# MCU.net
KiCad netlist of a schematic drawn in Altium Designer
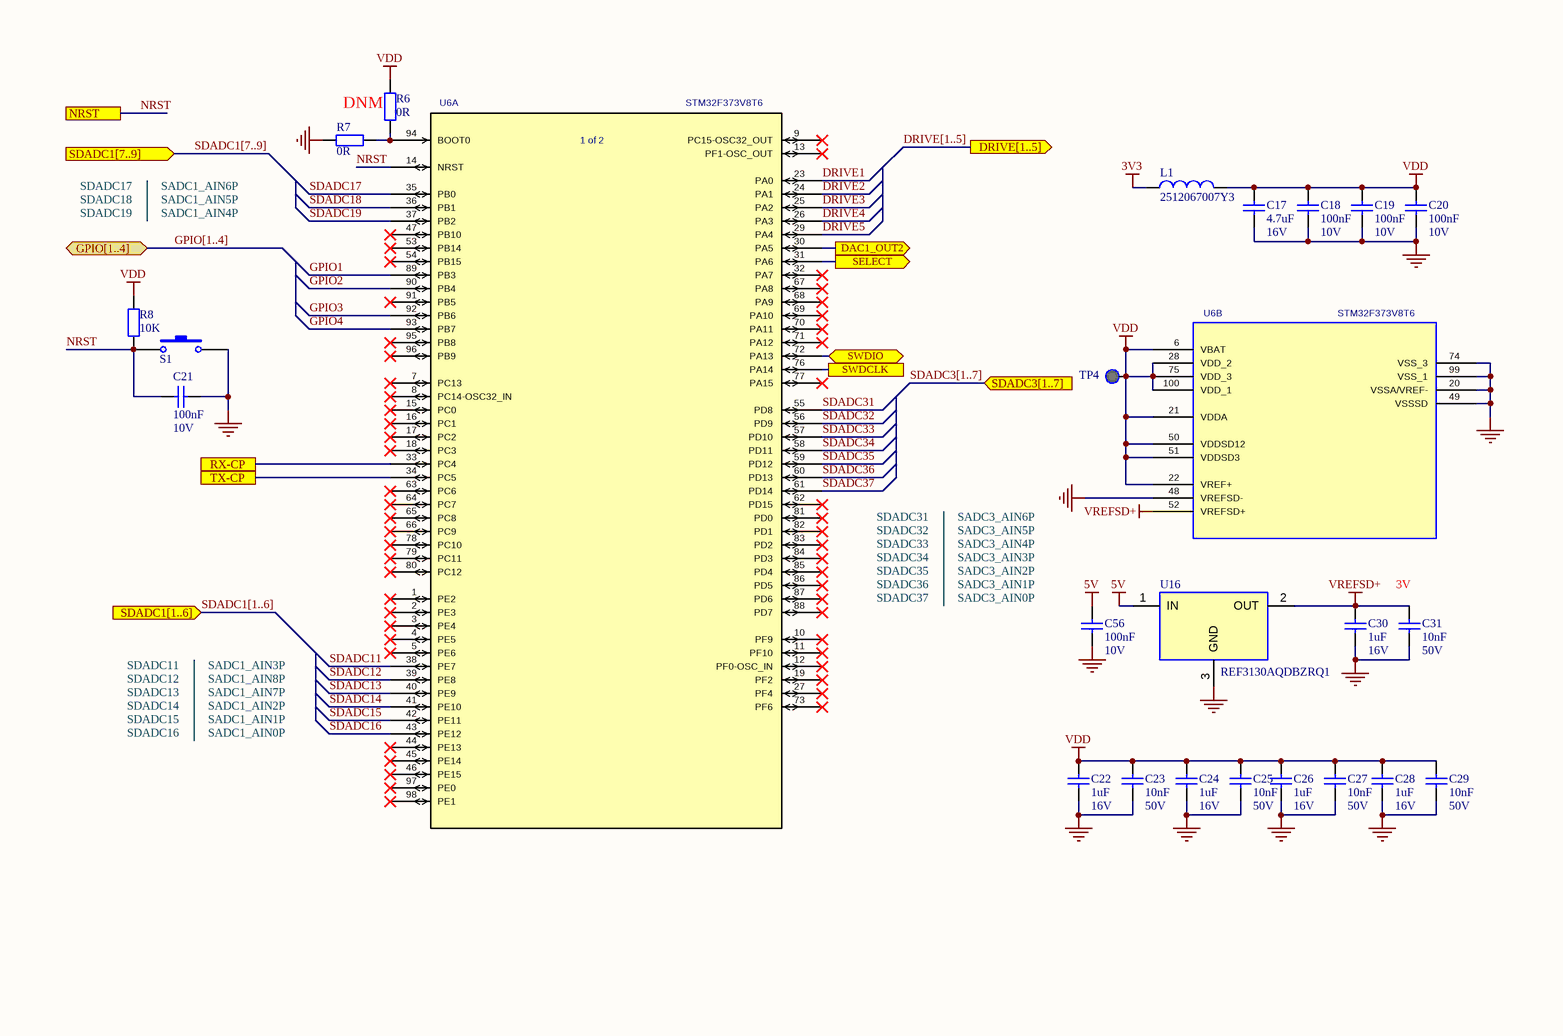
[diagram p0: MCU.SchDoc]

(export (version "E")
  (design (tool "Eeschema 10.0.6"))
  (components
    (comp (ref "C17")
      (value "Capacitor")
      (footprint "CAPC1608N")
      (fields
        (field (name "PART NUMBER") "CAP-000000047")
        (field (name "VALUE 1") "4.7uF")
        (field (name "VALUE 2") "16V")
      )
      (libsource (lib "CMA") (part "Capacitor"))
    )
    (comp (ref "C18")
      (value "Capacitor")
      (footprint "CAPC1608N")
      (fields
        (field (name "PART NUMBER") "CAP-000000005")
        (field (name "VALUE 1") "100nF")
        (field (name "VALUE 2") "10V")
      )
      (libsource (lib "CMA") (part "Capacitor"))
    )
    (comp (ref "C19")
      (value "Capacitor")
      (footprint "CAPC1608N")
      (fields
        (field (name "PART NUMBER") "CAP-000000005")
        (field (name "VALUE 1") "100nF")
        (field (name "VALUE 2") "10V")
      )
      (libsource (lib "CMA") (part "Capacitor"))
    )
    (comp (ref "C20")
      (value "Capacitor")
      (footprint "CAPC1608N")
      (fields
        (field (name "PART NUMBER") "CAP-000000005")
        (field (name "VALUE 1") "100nF")
        (field (name "VALUE 2") "10V")
      )
      (libsource (lib "CMA") (part "Capacitor"))
    )
    (comp (ref "C21")
      (value "Capacitor")
      (footprint "CAPC1608N")
      (fields
        (field (name "PART NUMBER") "CAP-000000005")
        (field (name "VALUE 1") "100nF")
        (field (name "VALUE 2") "10V")
      )
      (libsource (lib "CMA") (part "Capacitor"))
    )
    (comp (ref "C22")
      (value "Capacitor")
      (footprint "CAPC1608N")
      (fields
        (field (name "PART NUMBER") "CAP-000000011")
        (field (name "VALUE 1") "1uF")
        (field (name "VALUE 2") "16V")
      )
      (libsource (lib "CMA") (part "Capacitor"))
    )
    (comp (ref "C23")
      (value "Capacitor")
      (footprint "CAPC1608N")
      (fields
        (field (name "PART NUMBER") "CAP-000000003")
        (field (name "VALUE 1") "10nF")
        (field (name "VALUE 2") "50V")
      )
      (libsource (lib "CMA") (part "Capacitor"))
    )
    (comp (ref "C24")
      (value "Capacitor")
      (footprint "CAPC1608N")
      (fields
        (field (name "PART NUMBER") "CAP-000000011")
        (field (name "VALUE 1") "1uF")
        (field (name "VALUE 2") "16V")
      )
      (libsource (lib "CMA") (part "Capacitor"))
    )
    (comp (ref "C25")
      (value "Capacitor")
      (footprint "CAPC1608N")
      (fields
        (field (name "PART NUMBER") "CAP-000000003")
        (field (name "VALUE 1") "10nF")
        (field (name "VALUE 2") "50V")
      )
      (libsource (lib "CMA") (part "Capacitor"))
    )
    (comp (ref "C26")
      (value "Capacitor")
      (footprint "CAPC1608N")
      (fields
        (field (name "PART NUMBER") "CAP-000000011")
        (field (name "VALUE 1") "1uF")
        (field (name "VALUE 2") "16V")
      )
      (libsource (lib "CMA") (part "Capacitor"))
    )
    (comp (ref "C27")
      (value "Capacitor")
      (footprint "CAPC1608N")
      (fields
        (field (name "PART NUMBER") "CAP-000000003")
        (field (name "VALUE 1") "10nF")
        (field (name "VALUE 2") "50V")
      )
      (libsource (lib "CMA") (part "Capacitor"))
    )
    (comp (ref "C28")
      (value "Capacitor")
      (footprint "CAPC1608N")
      (fields
        (field (name "PART NUMBER") "CAP-000000011")
        (field (name "VALUE 1") "1uF")
        (field (name "VALUE 2") "16V")
      )
      (libsource (lib "CMA") (part "Capacitor"))
    )
    (comp (ref "C29")
      (value "Capacitor")
      (footprint "CAPC1608N")
      (fields
        (field (name "PART NUMBER") "CAP-000000003")
        (field (name "VALUE 1") "10nF")
        (field (name "VALUE 2") "50V")
      )
      (libsource (lib "CMA") (part "Capacitor"))
    )
    (comp (ref "C30")
      (value "Capacitor")
      (footprint "CAPC1608N")
      (fields
        (field (name "PART NUMBER") "CAP-000000011")
        (field (name "VALUE 1") "1uF")
        (field (name "VALUE 2") "16V")
      )
      (libsource (lib "CMA") (part "Capacitor"))
    )
    (comp (ref "C31")
      (value "Capacitor")
      (footprint "CAPC1608N")
      (fields
        (field (name "PART NUMBER") "CAP-000000003")
        (field (name "VALUE 1") "10nF")
        (field (name "VALUE 2") "50V")
      )
      (libsource (lib "CMA") (part "Capacitor"))
    )
    (comp (ref "C56")
      (value "Capacitor")
      (footprint "CAPC1608N")
      (fields
        (field (name "PART NUMBER") "CAP-000000005")
        (field (name "VALUE 1") "100nF")
        (field (name "VALUE 2") "10V")
      )
      (libsource (lib "CMA") (part "Capacitor"))
    )
    (comp (ref "L1")
      (value "2512067007Y3")
      (footprint "INDC3216N")
      (fields (field (name "PART NUMBER") "FER-000000001"))
      (libsource (lib "CMA") (part "Inductor"))
    )
    (comp (ref "R6")
      (value "Resistor")
      (footprint "RESC1608N")
      (fields (field (name "PART NUMBER") "RES-000000103") (field (name "VALUE 1") "0R"))
      (libsource (lib "") (part "Resistor_1"))
    )
    (comp (ref "R7")
      (value "Resistor")
      (footprint "RESC1608N")
      (fields (field (name "PART NUMBER") "RES-000000103") (field (name "VALUE 1") "0R"))
      (libsource (lib "CMA") (part "Resistor"))
    )
    (comp (ref "R8")
      (value "Resistor")
      (footprint "RESC1608N")
      (fields (field (name "PART NUMBER") "RES-000000001") (field (name "VALUE 1") "10K"))
      (libsource (lib "") (part "Resistor_2"))
    )
    (comp (ref "S1")
      (value "FSM4JSMA")
      (footprint "FSM4")
      (fields (field (name "PART NUMBER") "SWC-000000004"))
      (libsource (lib "CMA") (part "SW-PB"))
    )
    (comp (ref "TP4")
      (value "Test Point")
      (footprint "TP")
      (fields (field (name "PART NUMBER") "MIS-000000003"))
      (libsource (lib "CMA") (part "TP"))
    )
    (comp (ref "U6")
      (value "STM32F373V8T6")
      (footprint "LQFP100")
      (fields (field (name "PART NUMBER") "MCU-000000001"))
      (libsource (lib "CMA") (part "STM32F373V8T6"))
    )
    (comp (ref "U16")
      (value "REF3130AQDBZRQ1")
      (footprint "SOT23-3N")
      (fields (field (name "PART NUMBER") "VRF-000000001"))
      (libsource (lib "CMA") (part "REF3133AQDBZRQ1"))
    )
  )
  (nets
    (net (code "2") (name "/DAC1_OUT2") (class "Default")
      (node (ref "U6") (pin "30") (pinfunction "PA5_30") (pintype "passive"))
    )
    (net (code "3") (name "/DRIVE1") (class "Default")
      (node (ref "U6") (pin "23") (pinfunction "PA0_23") (pintype "passive"))
    )
    (net (code "4") (name "/DRIVE2") (class "Default")
      (node (ref "U6") (pin "24") (pinfunction "PA1_24") (pintype "passive"))
    )
    (net (code "5") (name "/DRIVE3") (class "Default")
      (node (ref "U6") (pin "25") (pinfunction "PA2_25") (pintype "passive"))
    )
    (net (code "6") (name "/DRIVE4") (class "Default")
      (node (ref "U6") (pin "26") (pinfunction "PA3_26") (pintype "passive"))
    )
    (net (code "7") (name "/DRIVE5") (class "Default")
      (node (ref "U6") (pin "29") (pinfunction "PA4_29") (pintype "passive"))
    )
    (net (code "9") (name "/GPIO1") (class "Default")
      (node (ref "U6") (pin "89") (pinfunction "PB3_89") (pintype "passive"))
    )
    (net (code "10") (name "/GPIO2") (class "Default")
      (node (ref "U6") (pin "90") (pinfunction "PB4_90") (pintype "passive"))
    )
    (net (code "11") (name "/GPIO3") (class "Default")
      (node (ref "U6") (pin "92") (pinfunction "PB6_92") (pintype "passive"))
    )
    (net (code "12") (name "/GPIO4") (class "Default")
      (node (ref "U6") (pin "93") (pinfunction "PB7_93") (pintype "passive"))
    )
    (net (code "14") (name "/NRST") (class "Default")
      (node (ref "C21") (pin "2") (pinfunction "2_2") (pintype "passive"))
      (node (ref "R8") (pin "2") (pinfunction "2_2") (pintype "passive"))
      (node (ref "S1") (pin "1") (pinfunction "1_1") (pintype "passive"))
      (node (ref "U6") (pin "14") (pinfunction "NRST_14") (pintype "passive"))
    )
    (net (code "15") (name "/RX-CP") (class "Default")
      (node (ref "U6") (pin "33") (pinfunction "PC4_33") (pintype "passive"))
    )
    (net (code "19") (name "/SDADC11") (class "Default")
      (node (ref "U6") (pin "38") (pinfunction "PE7_38") (pintype "passive"))
    )
    (net (code "20") (name "/SDADC12") (class "Default")
      (node (ref "U6") (pin "39") (pinfunction "PE8_39") (pintype "passive"))
    )
    (net (code "21") (name "/SDADC13") (class "Default")
      (node (ref "U6") (pin "40") (pinfunction "PE9_40") (pintype "passive"))
    )
    (net (code "22") (name "/SDADC14") (class "Default")
      (node (ref "U6") (pin "41") (pinfunction "PE10_41") (pintype "passive"))
    )
    (net (code "23") (name "/SDADC15") (class "Default")
      (node (ref "U6") (pin "42") (pinfunction "PE11_42") (pintype "passive"))
    )
    (net (code "24") (name "/SDADC16") (class "Default")
      (node (ref "U6") (pin "43") (pinfunction "PE12_43") (pintype "passive"))
    )
    (net (code "25") (name "/SDADC17") (class "Default")
      (node (ref "U6") (pin "35") (pinfunction "PB0_35") (pintype "passive"))
    )
    (net (code "26") (name "/SDADC18") (class "Default")
      (node (ref "U6") (pin "36") (pinfunction "PB1_36") (pintype "passive"))
    )
    (net (code "27") (name "/SDADC19") (class "Default")
      (node (ref "U6") (pin "37") (pinfunction "PB2_37") (pintype "passive"))
    )
    (net (code "28") (name "/SDADC31") (class "Default")
      (node (ref "U6") (pin "55") (pinfunction "PD8_55") (pintype "passive"))
    )
    (net (code "29") (name "/SDADC32") (class "Default")
      (node (ref "U6") (pin "56") (pinfunction "PD9_56") (pintype "passive"))
    )
    (net (code "30") (name "/SDADC33") (class "Default")
      (node (ref "U6") (pin "57") (pinfunction "PD10_57") (pintype "passive"))
    )
    (net (code "31") (name "/SDADC34") (class "Default")
      (node (ref "U6") (pin "58") (pinfunction "PD11_58") (pintype "passive"))
    )
    (net (code "32") (name "/SDADC35") (class "Default")
      (node (ref "U6") (pin "59") (pinfunction "PD12_59") (pintype "passive"))
    )
    (net (code "33") (name "/SDADC36") (class "Default")
      (node (ref "U6") (pin "60") (pinfunction "PD13_60") (pintype "passive"))
    )
    (net (code "34") (name "/SDADC37") (class "Default")
      (node (ref "U6") (pin "61") (pinfunction "PD14_61") (pintype "passive"))
    )
    (net (code "35") (name "/SELECT") (class "Default")
      (node (ref "U6") (pin "31") (pinfunction "PA6_31") (pintype "passive"))
    )
    (net (code "36") (name "/SWDCLK") (class "Default")
      (node (ref "U6") (pin "76") (pinfunction "PA14_76") (pintype "passive"))
    )
    (net (code "37") (name "/SWDIO") (class "Default")
      (node (ref "U6") (pin "72") (pinfunction "PA13_72") (pintype "passive"))
    )
    (net (code "38") (name "/TX-CP") (class "Default")
      (node (ref "U6") (pin "34") (pinfunction "PC5_34") (pintype "passive"))
    )
    (net (code "39") (name "3V3") (class "Default")
      (node (ref "L1") (pin "1") (pinfunction "1_1") (pintype "passive"))
    )
    (net (code "40") (name "5V") (class "Default")
      (node (ref "C56") (pin "2") (pinfunction "2_2") (pintype "passive"))
      (node (ref "U16") (pin "1") (pinfunction "IN_1") (pintype "passive"))
    )
    (net (code "41") (name "GND") (class "Default")
      (node (ref "C17") (pin "2") (pinfunction "2_2") (pintype "passive"))
      (node (ref "C18") (pin "1") (pinfunction "1_1") (pintype "passive"))
      (node (ref "C19") (pin "1") (pinfunction "1_1") (pintype "passive"))
      (node (ref "C20") (pin "1") (pinfunction "1_1") (pintype "passive"))
      (node (ref "C21") (pin "1") (pinfunction "1_1") (pintype "passive"))
      (node (ref "C22") (pin "1") (pinfunction "1_1") (pintype "passive"))
      (node (ref "C23") (pin "1") (pinfunction "1_1") (pintype "passive"))
      (node (ref "C24") (pin "1") (pinfunction "1_1") (pintype "passive"))
      (node (ref "C25") (pin "1") (pinfunction "1_1") (pintype "passive"))
      (node (ref "C26") (pin "1") (pinfunction "1_1") (pintype "passive"))
      (node (ref "C27") (pin "1") (pinfunction "1_1") (pintype "passive"))
      (node (ref "C28") (pin "1") (pinfunction "1_1") (pintype "passive"))
      (node (ref "C29") (pin "1") (pinfunction "1_1") (pintype "passive"))
      (node (ref "C30") (pin "1") (pinfunction "1_1") (pintype "passive"))
      (node (ref "C31") (pin "1") (pinfunction "1_1") (pintype "passive"))
      (node (ref "C56") (pin "1") (pinfunction "1_1") (pintype "passive"))
      (node (ref "R7") (pin "1") (pinfunction "1_1") (pintype "passive"))
      (node (ref "S1") (pin "2") (pinfunction "2_2") (pintype "passive"))
      (node (ref "U16") (pin "3") (pinfunction "GND_3") (pintype "passive"))
      (node (ref "U6") (pin "20") (pinfunction "VSSA/VREF-_20") (pintype "power_in"))
      (node (ref "U6") (pin "48") (pinfunction "VREFSD-_48") (pintype "power_in"))
      (node (ref "U6") (pin "49") (pinfunction "VSSSD_49") (pintype "power_in"))
      (node (ref "U6") (pin "74") (pinfunction "VSS_3_74") (pintype "power_in"))
      (node (ref "U6") (pin "99") (pinfunction "VSS_1_99") (pintype "power_in"))
    )
    (net (code "42") (name "Net-(U6A-BOOT0)") (class "Default")
      (node (ref "R6") (pin "1") (pinfunction "1_1") (pintype "passive"))
      (node (ref "R7") (pin "2") (pinfunction "2_2") (pintype "passive"))
      (node (ref "U6") (pin "94") (pinfunction "BOOT0_94") (pintype "passive"))
    )
    (net (code "43") (name "VDD") (class "Default")
      (node (ref "C17") (pin "1") (pinfunction "1_1") (pintype "passive"))
      (node (ref "C18") (pin "2") (pinfunction "2_2") (pintype "passive"))
      (node (ref "C19") (pin "2") (pinfunction "2_2") (pintype "passive"))
      (node (ref "C20") (pin "2") (pinfunction "2_2") (pintype "passive"))
      (node (ref "C22") (pin "2") (pinfunction "2_2") (pintype "passive"))
      (node (ref "C23") (pin "2") (pinfunction "2_2") (pintype "passive"))
      (node (ref "C24") (pin "2") (pinfunction "2_2") (pintype "passive"))
      (node (ref "C25") (pin "2") (pinfunction "2_2") (pintype "passive"))
      (node (ref "C26") (pin "2") (pinfunction "2_2") (pintype "passive"))
      (node (ref "C27") (pin "2") (pinfunction "2_2") (pintype "passive"))
      (node (ref "C28") (pin "2") (pinfunction "2_2") (pintype "passive"))
      (node (ref "C29") (pin "2") (pinfunction "2_2") (pintype "passive"))
      (node (ref "L1") (pin "2") (pinfunction "2_2") (pintype "passive"))
      (node (ref "R6") (pin "2") (pinfunction "2_2") (pintype "passive"))
      (node (ref "R8") (pin "1") (pinfunction "1_1") (pintype "passive"))
      (node (ref "TP4") (pin "1") (pinfunction "1_1") (pintype "passive"))
      (node (ref "U6") (pin "100") (pinfunction "VDD_1_100") (pintype "power_in"))
      (node (ref "U6") (pin "21") (pinfunction "VDDA_21") (pintype "power_in"))
      (node (ref "U6") (pin "22") (pinfunction "VREF+_22") (pintype "power_in"))
      (node (ref "U6") (pin "28") (pinfunction "VDD_2_28") (pintype "power_in"))
      (node (ref "U6") (pin "50") (pinfunction "VDDSD12_50") (pintype "power_in"))
      (node (ref "U6") (pin "51") (pinfunction "VDDSD3_51") (pintype "power_in"))
      (node (ref "U6") (pin "6") (pinfunction "VBAT_6") (pintype "power_in"))
      (node (ref "U6") (pin "75") (pinfunction "VDD_3_75") (pintype "power_in"))
    )
    (net (code "44") (name "VREFSD+") (class "Default")
      (node (ref "C30") (pin "2") (pinfunction "2_2") (pintype "passive"))
      (node (ref "C31") (pin "2") (pinfunction "2_2") (pintype "passive"))
      (node (ref "U16") (pin "2") (pinfunction "OUT_2") (pintype "passive"))
      (node (ref "U6") (pin "52") (pinfunction "VREFSD+_52") (pintype "power_in"))
    )
    (net (code "45") (name "unconnected-(U6A-PA7-Pad32)") (class "Default")
      (node (ref "U6") (pin "32") (pinfunction "PA7_32") (pintype "passive+no_connect"))
    )
    (net (code "46") (name "unconnected-(U6A-PA8-Pad67)") (class "Default")
      (node (ref "U6") (pin "67") (pinfunction "PA8_67") (pintype "passive+no_connect"))
    )
    (net (code "47") (name "unconnected-(U6A-PA9-Pad68)") (class "Default")
      (node (ref "U6") (pin "68") (pinfunction "PA9_68") (pintype "passive+no_connect"))
    )
    (net (code "48") (name "unconnected-(U6A-PA10-Pad69)") (class "Default")
      (node (ref "U6") (pin "69") (pinfunction "PA10_69") (pintype "passive+no_connect"))
    )
    (net (code "49") (name "unconnected-(U6A-PA11-Pad70)") (class "Default")
      (node (ref "U6") (pin "70") (pinfunction "PA11_70") (pintype "passive+no_connect"))
    )
    (net (code "50") (name "unconnected-(U6A-PA12-Pad71)") (class "Default")
      (node (ref "U6") (pin "71") (pinfunction "PA12_71") (pintype "passive+no_connect"))
    )
    (net (code "51") (name "unconnected-(U6A-PA15-Pad77)") (class "Default")
      (node (ref "U6") (pin "77") (pinfunction "PA15_77") (pintype "passive+no_connect"))
    )
    (net (code "52") (name "unconnected-(U6A-PB5-Pad91)") (class "Default")
      (node (ref "U6") (pin "91") (pinfunction "PB5_91") (pintype "passive+no_connect"))
    )
    (net (code "53") (name "unconnected-(U6A-PB8-Pad95)") (class "Default")
      (node (ref "U6") (pin "95") (pinfunction "PB8_95") (pintype "passive+no_connect"))
    )
    (net (code "54") (name "unconnected-(U6A-PB9-Pad96)") (class "Default")
      (node (ref "U6") (pin "96") (pinfunction "PB9_96") (pintype "passive+no_connect"))
    )
    (net (code "55") (name "unconnected-(U6A-PB10-Pad47)") (class "Default")
      (node (ref "U6") (pin "47") (pinfunction "PB10_47") (pintype "passive+no_connect"))
    )
    (net (code "56") (name "unconnected-(U6A-PB14-Pad53)") (class "Default")
      (node (ref "U6") (pin "53") (pinfunction "PB14_53") (pintype "passive+no_connect"))
    )
    (net (code "57") (name "unconnected-(U6A-PB15-Pad54)") (class "Default")
      (node (ref "U6") (pin "54") (pinfunction "PB15_54") (pintype "passive+no_connect"))
    )
    (net (code "58") (name "unconnected-(U6A-PC0-Pad15)") (class "Default")
      (node (ref "U6") (pin "15") (pinfunction "PC0_15") (pintype "passive+no_connect"))
    )
    (net (code "59") (name "unconnected-(U6A-PC1-Pad16)") (class "Default")
      (node (ref "U6") (pin "16") (pinfunction "PC1_16") (pintype "passive+no_connect"))
    )
    (net (code "60") (name "unconnected-(U6A-PC2-Pad17)") (class "Default")
      (node (ref "U6") (pin "17") (pinfunction "PC2_17") (pintype "passive+no_connect"))
    )
    (net (code "61") (name "unconnected-(U6A-PC3-Pad18)") (class "Default")
      (node (ref "U6") (pin "18") (pinfunction "PC3_18") (pintype "passive+no_connect"))
    )
    (net (code "62") (name "unconnected-(U6A-PC6-Pad63)") (class "Default")
      (node (ref "U6") (pin "63") (pinfunction "PC6_63") (pintype "passive+no_connect"))
    )
    (net (code "63") (name "unconnected-(U6A-PC7-Pad64)") (class "Default")
      (node (ref "U6") (pin "64") (pinfunction "PC7_64") (pintype "passive+no_connect"))
    )
    (net (code "64") (name "unconnected-(U6A-PC8-Pad65)") (class "Default")
      (node (ref "U6") (pin "65") (pinfunction "PC8_65") (pintype "passive+no_connect"))
    )
    (net (code "65") (name "unconnected-(U6A-PC9-Pad66)") (class "Default")
      (node (ref "U6") (pin "66") (pinfunction "PC9_66") (pintype "passive+no_connect"))
    )
    (net (code "66") (name "unconnected-(U6A-PC10-Pad78)") (class "Default")
      (node (ref "U6") (pin "78") (pinfunction "PC10_78") (pintype "passive+no_connect"))
    )
    (net (code "67") (name "unconnected-(U6A-PC11-Pad79)") (class "Default")
      (node (ref "U6") (pin "79") (pinfunction "PC11_79") (pintype "passive+no_connect"))
    )
    (net (code "68") (name "unconnected-(U6A-PC12-Pad80)") (class "Default")
      (node (ref "U6") (pin "80") (pinfunction "PC12_80") (pintype "passive+no_connect"))
    )
    (net (code "69") (name "unconnected-(U6A-PC13-Pad7)") (class "Default")
      (node (ref "U6") (pin "7") (pinfunction "PC13_7") (pintype "passive+no_connect"))
    )
    (net (code "70") (name "unconnected-(U6A-PC14-OSC32_IN-Pad8)") (class "Default")
      (node (ref "U6") (pin "8") (pinfunction "PC14-OSC32_IN_8") (pintype "passive+no_connect"))
    )
    (net (code "71") (name "unconnected-(U6A-PC15-OSC32_OUT-Pad9)") (class "Default")
      (node (ref "U6") (pin "9") (pinfunction "PC15-OSC32_OUT_9") (pintype "passive+no_connect"))
    )
    (net (code "72") (name "unconnected-(U6A-PD0-Pad81)") (class "Default")
      (node (ref "U6") (pin "81") (pinfunction "PD0_81") (pintype "passive+no_connect"))
    )
    (net (code "73") (name "unconnected-(U6A-PD1-Pad82)") (class "Default")
      (node (ref "U6") (pin "82") (pinfunction "PD1_82") (pintype "passive+no_connect"))
    )
    (net (code "74") (name "unconnected-(U6A-PD2-Pad83)") (class "Default")
      (node (ref "U6") (pin "83") (pinfunction "PD2_83") (pintype "passive+no_connect"))
    )
    (net (code "75") (name "unconnected-(U6A-PD3-Pad84)") (class "Default")
      (node (ref "U6") (pin "84") (pinfunction "PD3_84") (pintype "passive+no_connect"))
    )
    (net (code "76") (name "unconnected-(U6A-PD4-Pad85)") (class "Default")
      (node (ref "U6") (pin "85") (pinfunction "PD4_85") (pintype "passive+no_connect"))
    )
    (net (code "77") (name "unconnected-(U6A-PD5-Pad86)") (class "Default")
      (node (ref "U6") (pin "86") (pinfunction "PD5_86") (pintype "passive+no_connect"))
    )
    (net (code "78") (name "unconnected-(U6A-PD6-Pad87)") (class "Default")
      (node (ref "U6") (pin "87") (pinfunction "PD6_87") (pintype "passive+no_connect"))
    )
    (net (code "79") (name "unconnected-(U6A-PD7-Pad88)") (class "Default")
      (node (ref "U6") (pin "88") (pinfunction "PD7_88") (pintype "passive+no_connect"))
    )
    (net (code "80") (name "unconnected-(U6A-PD15-Pad62)") (class "Default")
      (node (ref "U6") (pin "62") (pinfunction "PD15_62") (pintype "passive+no_connect"))
    )
    (net (code "81") (name "unconnected-(U6A-PE0-Pad97)") (class "Default")
      (node (ref "U6") (pin "97") (pinfunction "PE0_97") (pintype "passive+no_connect"))
    )
    (net (code "82") (name "unconnected-(U6A-PE1-Pad98)") (class "Default")
      (node (ref "U6") (pin "98") (pinfunction "PE1_98") (pintype "passive+no_connect"))
    )
    (net (code "83") (name "unconnected-(U6A-PE2-Pad1)") (class "Default")
      (node (ref "U6") (pin "1") (pinfunction "PE2_1") (pintype "passive+no_connect"))
    )
    (net (code "84") (name "unconnected-(U6A-PE3-Pad2)") (class "Default")
      (node (ref "U6") (pin "2") (pinfunction "PE3_2") (pintype "passive+no_connect"))
    )
    (net (code "85") (name "unconnected-(U6A-PE4-Pad3)") (class "Default")
      (node (ref "U6") (pin "3") (pinfunction "PE4_3") (pintype "passive+no_connect"))
    )
    (net (code "86") (name "unconnected-(U6A-PE5-Pad4)") (class "Default")
      (node (ref "U6") (pin "4") (pinfunction "PE5_4") (pintype "passive+no_connect"))
    )
    (net (code "87") (name "unconnected-(U6A-PE6-Pad5)") (class "Default")
      (node (ref "U6") (pin "5") (pinfunction "PE6_5") (pintype "passive+no_connect"))
    )
    (net (code "88") (name "unconnected-(U6A-PE13-Pad44)") (class "Default")
      (node (ref "U6") (pin "44") (pinfunction "PE13_44") (pintype "passive+no_connect"))
    )
    (net (code "89") (name "unconnected-(U6A-PE14-Pad45)") (class "Default")
      (node (ref "U6") (pin "45") (pinfunction "PE14_45") (pintype "passive+no_connect"))
    )
    (net (code "90") (name "unconnected-(U6A-PE15-Pad46)") (class "Default")
      (node (ref "U6") (pin "46") (pinfunction "PE15_46") (pintype "passive+no_connect"))
    )
    (net (code "91") (name "unconnected-(U6A-PF0-OSC_IN-Pad12)") (class "Default")
      (node (ref "U6") (pin "12") (pinfunction "PF0-OSC_IN_12") (pintype "passive+no_connect"))
    )
    (net (code "92") (name "unconnected-(U6A-PF1-OSC_OUT-Pad13)") (class "Default")
      (node (ref "U6") (pin "13") (pinfunction "PF1-OSC_OUT_13") (pintype "passive+no_connect"))
    )
    (net (code "93") (name "unconnected-(U6A-PF2-Pad19)") (class "Default")
      (node (ref "U6") (pin "19") (pinfunction "PF2_19") (pintype "passive+no_connect"))
    )
    (net (code "94") (name "unconnected-(U6A-PF4-Pad27)") (class "Default")
      (node (ref "U6") (pin "27") (pinfunction "PF4_27") (pintype "passive+no_connect"))
    )
    (net (code "95") (name "unconnected-(U6A-PF6-Pad73)") (class "Default")
      (node (ref "U6") (pin "73") (pinfunction "PF6_73") (pintype "passive+no_connect"))
    )
    (net (code "96") (name "unconnected-(U6A-PF9-Pad10)") (class "Default")
      (node (ref "U6") (pin "10") (pinfunction "PF9_10") (pintype "passive+no_connect"))
    )
    (net (code "97") (name "unconnected-(U6A-PF10-Pad11)") (class "Default")
      (node (ref "U6") (pin "11") (pinfunction "PF10_11") (pintype "passive+no_connect"))
    )
  )
)
